# AFE.net
KiCad netlist of a schematic drawn in Altium Designer
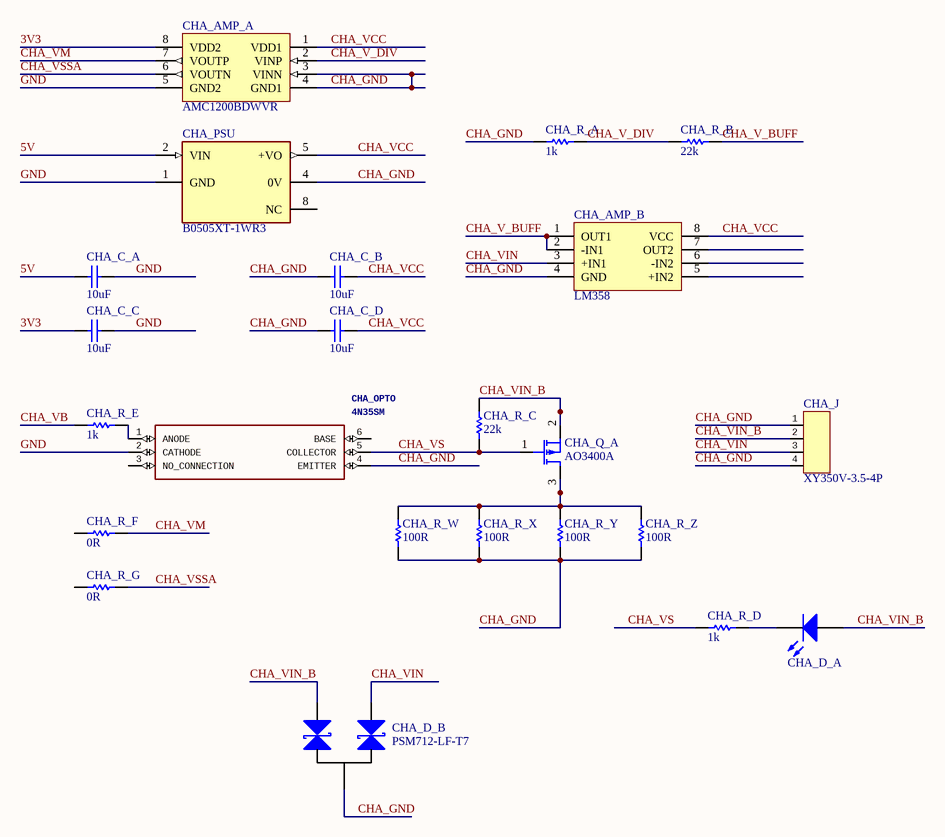
[diagram p0: AFE.SchDoc]

(export (version "E")
  (design (tool "Eeschema 10.0.6"))
  (components
    (comp (ref "CHA_AMP_A")
      (value "AMC1200BDWVR")
      (footprint "FOOTPRINTS:SOIC-8-P1.27-W7.5")
      (description "U - IC - 100KHz ISOLATION AMPLIFIER")
      (fields (field (name "LCSC PART #") "C79905"))
      (libsource (lib "JLC_PCB") (part "AMC1200BDWVR"))
    )
    (comp (ref "CHA_AMP_B")
      (value "LM358")
      (footprint "FOOTPRINTS:SOIC-8-P1.27-W3.5")
      (description "U - IC - OP AMP (DUAL)")
      (fields (field (name "LCSC PART #") "C63813"))
      (libsource (lib "JLC_PCB") (part "LMV358IDR"))
    )
    (comp (ref "CHA_C_A")
      (value "10uF")
      (footprint "C_0603")
      (description "C - CAPACITOR - MLCC - 10uF - 25V - 0603")
      (fields (field (name "LCSC PART #") "C96446") (field (name "Comment") "CL10A106MA8NRNC"))
      (libsource (lib "JLC_PCB") (part "CL10A106MA8NRNC"))
    )
    (comp (ref "CHA_C_B")
      (value "10uF")
      (footprint "C_0603")
      (description "C - CAPACITOR - MLCC - 10uF - 25V - 0603")
      (fields (field (name "LCSC PART #") "C96446") (field (name "Comment") "CL10A106MA8NRNC"))
      (libsource (lib "JLC_PCB") (part "CL10A106MA8NRNC"))
    )
    (comp (ref "CHA_C_C")
      (value "10uF")
      (footprint "C_0603")
      (description "C - CAPACITOR - MLCC - 10uF - 25V - 0603")
      (fields (field (name "LCSC PART #") "C96446") (field (name "Comment") "CL10A106MA8NRNC"))
      (libsource (lib "JLC_PCB") (part "CL10A106MA8NRNC"))
    )
    (comp (ref "CHA_C_D")
      (value "10uF")
      (footprint "C_0603")
      (description "C - CAPACITOR - MLCC - 10uF - 25V - 0603")
      (fields (field (name "LCSC PART #") "C96446") (field (name "Comment") "CL10A106MA8NRNC"))
      (libsource (lib "JLC_PCB") (part "CL10A106MA8NRNC"))
    )
    (comp (ref "CHA_D_A")
      (value "KT-0603R")
      (footprint "D_0603")
      (description "D - LED - 0603 - Red")
      (fields (field (name "LCSC PART #") "C2286"))
      (libsource (lib "JLC_PCB") (part "KT-0603R"))
    )
    (comp (ref "CHA_D_B")
      (value "PSM712-LF-T7")
      (footprint "TO-236AB")
      (description "D - DIODE - TVS x2 - 7.2V")
      (fields (field (name "LCSC PART #") "C32677"))
      (libsource (lib "JLC_PCB") (part "PSM712-LF-T7"))
    )
    (comp (ref "CHA_J")
      (value "XY350V-3.5-4P")
      (footprint "XY350V-3.5-4P")
      (description "J - JACK - TERMINAL - 4P - RIGHT - MALE")
      (fields (field (name "LCSC PART #") "C557656"))
      (libsource (lib "JLC_PCB") (part "XY350V-3.5-4P"))
    )
    (comp (ref "CHA_OPTO")
      (value "4N35SM")
      (footprint "SOT254P916X508-6N")
      (description "Q - OPTOCOUPLER - 4170 V - 100% CTR")
      (fields (field (name "LCSC PART #") "C258228"))
      (libsource (lib "JLC_PCB") (part "4N35SM"))
    )
    (comp (ref "CHA_PSU")
      (value "B0505XT-1WR3")
      (footprint "CONV_B0512XT-1WR3")
      (description "T - Isolated Module DC DC Converter 5 -> 5V 200mA - DIP")
      (fields (field (name "LCSC PART #") "C19188495") (field (name "MF") "EVISUN"))
      (libsource (lib "JLC_PCB") (part "B0505XT-1WR3"))
    )
    (comp (ref "CHA_Q_A")
      (value "AO3400A")
      (footprint "TO-236AB")
      (description "Q - TRANSISTOR - MOSFET (P) - 20V - 3.4A - 0.26 Ohm")
      (fields (field (name "LCSC PART #") "C20917"))
      (libsource (lib "JLC_PCB") (part "AO3400A"))
    )
    (comp (ref "CHA_R_A")
      (value "1k")
      (footprint "R_0603")
      (description "R - RESISTOR - SMD - 1k - 1% - 0603")
      (fields (field (name "LCSC PART #") "C21190") (field (name "Comment") "0603WAF1001T5E"))
      (libsource (lib "JLC_PCB") (part "0603WAF1001T5E"))
    )
    (comp (ref "CHA_R_B")
      (value "22k")
      (footprint "R_0603")
      (description "R - RESISTOR - SMD - 22k - 1% - 0603")
      (fields (field (name "LCSC PART #") "C31850") (field (name "Comment") "0603WAF2202T5E"))
      (libsource (lib "JLC_PCB") (part "0603WAF2202T5E"))
    )
    (comp (ref "CHA_R_C")
      (value "22k")
      (footprint "R_0603")
      (description "R - RESISTOR - SMD - 22k - 1% - 0603")
      (fields (field (name "LCSC PART #") "C31850") (field (name "Comment") "0603WAF2202T5E"))
      (libsource (lib "JLC_PCB") (part "0603WAF2202T5E"))
    )
    (comp (ref "CHA_R_D")
      (value "1k")
      (footprint "R_0603")
      (description "R - RESISTOR - SMD - 1k - 1% - 0603")
      (fields (field (name "LCSC PART #") "C21190") (field (name "Comment") "0603WAF1001T5E"))
      (libsource (lib "JLC_PCB") (part "0603WAF1001T5E"))
    )
    (comp (ref "CHA_R_E")
      (value "1k")
      (footprint "R_0603")
      (description "R - RESISTOR - SMD - 1k - 1% - 0603")
      (fields (field (name "LCSC PART #") "C21190") (field (name "Comment") "0603WAF1001T5E"))
      (libsource (lib "JLC_PCB") (part "0603WAF1001T5E"))
    )
    (comp (ref "CHA_R_F")
      (value "0R")
      (footprint "R_0603")
      (description "R - RESISTOR - SMD - 0R - 1% - 0603")
      (fields (field (name "LCSC PART #") "C21189") (field (name "Comment") "0603WAF0000T5E"))
      (libsource (lib "JLC_PCB") (part "0603WAF0000T5E"))
    )
    (comp (ref "CHA_R_G")
      (value "0R")
      (footprint "R_0603")
      (description "R - RESISTOR - SMD - 0R - 1% - 0603")
      (fields (field (name "LCSC PART #") "C21189") (field (name "Comment") "0603WAF0000T5E"))
      (libsource (lib "JLC_PCB") (part "0603WAF0000T5E"))
    )
    (comp (ref "CHA_R_W")
      (value "100R")
      (footprint "R_1206")
      (description "R - RESISTOR - SMD - 100R - 1% - 1206")
      (fields (field (name "LCSC PART #") "C17901") (field (name "Comment") "1206W4F1000T5E"))
      (libsource (lib "JLC_PCB") (part "1206W4F1000T5E"))
    )
    (comp (ref "CHA_R_X")
      (value "100R")
      (footprint "R_1206")
      (description "R - RESISTOR - SMD - 100R - 1% - 1206")
      (fields (field (name "LCSC PART #") "C17901") (field (name "Comment") "1206W4F1000T5E"))
      (libsource (lib "JLC_PCB") (part "1206W4F1000T5E"))
    )
    (comp (ref "CHA_R_Y")
      (value "100R")
      (footprint "R_1206")
      (description "R - RESISTOR - SMD - 100R - 1% - 1206")
      (fields (field (name "LCSC PART #") "C17901") (field (name "Comment") "1206W4F1000T5E"))
      (libsource (lib "JLC_PCB") (part "1206W4F1000T5E"))
    )
    (comp (ref "CHA_R_Z")
      (value "100R")
      (footprint "R_1206")
      (description "R - RESISTOR - SMD - 100R - 1% - 1206")
      (fields (field (name "LCSC PART #") "C17901") (field (name "Comment") "1206W4F1000T5E"))
      (libsource (lib "JLC_PCB") (part "1206W4F1000T5E"))
    )
  )
  (nets
    (net (code "1") (name "/3V3") (class "Default")
      (node (ref "CHA_AMP_A") (pin "8") (pinfunction "VDD2_8") (pintype "passive"))
      (node (ref "CHA_C_C") (pin "2") (pinfunction "2_2") (pintype "passive"))
    )
    (net (code "2") (name "/5V") (class "Default")
      (node (ref "CHA_C_A") (pin "2") (pinfunction "2_2") (pintype "passive"))
      (node (ref "CHA_PSU") (pin "2") (pinfunction "VIN_2") (pintype "input"))
    )
    (net (code "3") (name "/CHA_GND") (class "Default")
      (node (ref "CHA_AMP_A") (pin "3") (pinfunction "VINN_3") (pintype "input"))
      (node (ref "CHA_AMP_A") (pin "4") (pinfunction "GND1_4") (pintype "power_in"))
      (node (ref "CHA_AMP_B") (pin "4") (pinfunction "GND_4") (pintype "passive"))
      (node (ref "CHA_C_B") (pin "2") (pinfunction "2_2") (pintype "passive"))
      (node (ref "CHA_C_D") (pin "2") (pinfunction "2_2") (pintype "passive"))
      (node (ref "CHA_D_B") (pin "3") (pinfunction "A_3") (pintype "passive"))
      (node (ref "CHA_J") (pin "1") (pinfunction "1_1") (pintype "passive"))
      (node (ref "CHA_J") (pin "4") (pinfunction "4_4") (pintype "passive"))
      (node (ref "CHA_OPTO") (pin "4") (pinfunction "EMITTER_4") (pintype "bidirectional"))
      (node (ref "CHA_PSU") (pin "4") (pinfunction "0V_4") (pintype "passive"))
      (node (ref "CHA_R_A") (pin "1") (pinfunction "1_1") (pintype "passive"))
      (node (ref "CHA_R_W") (pin "1") (pinfunction "1_1") (pintype "passive"))
      (node (ref "CHA_R_X") (pin "1") (pinfunction "1_1") (pintype "passive"))
      (node (ref "CHA_R_Y") (pin "1") (pinfunction "1_1") (pintype "passive"))
      (node (ref "CHA_R_Z") (pin "1") (pinfunction "1_1") (pintype "passive"))
    )
    (net (code "4") (name "/CHA_VB") (class "Default")
      (node (ref "CHA_R_E") (pin "1") (pinfunction "1_1") (pintype "passive"))
    )
    (net (code "5") (name "/CHA_VCC") (class "Default")
      (node (ref "CHA_AMP_A") (pin "1") (pinfunction "VDD1_1") (pintype "passive"))
      (node (ref "CHA_AMP_B") (pin "8") (pinfunction "VCC_8") (pintype "passive"))
      (node (ref "CHA_C_B") (pin "1") (pinfunction "1_1") (pintype "passive"))
      (node (ref "CHA_C_D") (pin "1") (pinfunction "1_1") (pintype "passive"))
      (node (ref "CHA_PSU") (pin "5") (pinfunction "+VO_5") (pintype "output"))
    )
    (net (code "6") (name "/CHA_VIN") (class "Default")
      (node (ref "CHA_AMP_B") (pin "3") (pinfunction "+IN1_3") (pintype "passive"))
      (node (ref "CHA_D_B") (pin "2") (pinfunction "K_2") (pintype "passive"))
      (node (ref "CHA_J") (pin "3") (pinfunction "3_3") (pintype "passive"))
    )
    (net (code "7") (name "/CHA_VIN_B") (class "Default")
      (node (ref "CHA_D_A") (pin "2") (pinfunction "A_2") (pintype "passive"))
      (node (ref "CHA_D_B") (pin "1") (pinfunction "K_1") (pintype "passive"))
      (node (ref "CHA_J") (pin "2") (pinfunction "2_2") (pintype "passive"))
      (node (ref "CHA_Q_A") (pin "2") (pinfunction "S_2") (pintype "passive"))
      (node (ref "CHA_R_C") (pin "2") (pinfunction "2_2") (pintype "passive"))
    )
    (net (code "8") (name "/CHA_VM") (class "Default")
      (node (ref "CHA_AMP_A") (pin "7") (pinfunction "VOUTP_7") (pintype "output"))
      (node (ref "CHA_R_F") (pin "2") (pinfunction "2_2") (pintype "passive"))
    )
    (net (code "9") (name "/CHA_VS") (class "Default")
      (node (ref "CHA_OPTO") (pin "5") (pinfunction "COLLECTOR_5") (pintype "bidirectional"))
      (node (ref "CHA_Q_A") (pin "1") (pinfunction "G_1") (pintype "passive"))
      (node (ref "CHA_R_C") (pin "1") (pinfunction "1_1") (pintype "passive"))
      (node (ref "CHA_R_D") (pin "1") (pinfunction "1_1") (pintype "passive"))
    )
    (net (code "10") (name "/CHA_VSSA") (class "Default")
      (node (ref "CHA_AMP_A") (pin "6") (pinfunction "VOUTN_6") (pintype "output"))
      (node (ref "CHA_R_G") (pin "2") (pinfunction "2_2") (pintype "passive"))
    )
    (net (code "11") (name "/CHA_V_BUFF") (class "Default")
      (node (ref "CHA_AMP_B") (pin "1") (pinfunction "OUT1_1") (pintype "passive"))
      (node (ref "CHA_AMP_B") (pin "2") (pinfunction "-IN1_2") (pintype "passive"))
      (node (ref "CHA_R_B") (pin "2") (pinfunction "2_2") (pintype "passive"))
    )
    (net (code "12") (name "/CHA_V_DIV") (class "Default")
      (node (ref "CHA_AMP_A") (pin "2") (pinfunction "VINP_2") (pintype "input"))
      (node (ref "CHA_R_A") (pin "2") (pinfunction "2_2") (pintype "passive"))
      (node (ref "CHA_R_B") (pin "1") (pinfunction "1_1") (pintype "passive"))
    )
    (net (code "13") (name "/GND") (class "Default")
      (node (ref "CHA_AMP_A") (pin "5") (pinfunction "GND2_5") (pintype "power_in"))
      (node (ref "CHA_C_A") (pin "1") (pinfunction "1_1") (pintype "passive"))
      (node (ref "CHA_C_C") (pin "1") (pinfunction "1_1") (pintype "passive"))
      (node (ref "CHA_OPTO") (pin "2") (pinfunction "CATHODE_2") (pintype "bidirectional"))
      (node (ref "CHA_PSU") (pin "1") (pinfunction "GND_1") (pintype "power_in"))
    )
    (net (code "14") (name "Net-(CHA_D_A-K)") (class "Default")
      (node (ref "CHA_D_A") (pin "1") (pinfunction "K_1") (pintype "passive"))
      (node (ref "CHA_R_D") (pin "2") (pinfunction "2_2") (pintype "passive"))
    )
    (net (code "15") (name "Net-(CHA_OPTO-ANODE)") (class "Default")
      (node (ref "CHA_OPTO") (pin "1") (pinfunction "ANODE_1") (pintype "bidirectional"))
      (node (ref "CHA_R_E") (pin "2") (pinfunction "2_2") (pintype "passive"))
    )
    (net (code "16") (name "Net-(CHA_Q_A-D)") (class "Default")
      (node (ref "CHA_Q_A") (pin "3") (pinfunction "D_3") (pintype "passive"))
      (node (ref "CHA_R_W") (pin "2") (pinfunction "2_2") (pintype "passive"))
      (node (ref "CHA_R_X") (pin "2") (pinfunction "2_2") (pintype "passive"))
      (node (ref "CHA_R_Y") (pin "2") (pinfunction "2_2") (pintype "passive"))
      (node (ref "CHA_R_Z") (pin "2") (pinfunction "2_2") (pintype "passive"))
    )
    (net (code "17") (name "unconnected-(CHA_AMP_B-+IN2-Pad5)") (class "Default")
      (node (ref "CHA_AMP_B") (pin "5") (pinfunction "+IN2_5") (pintype "passive"))
    )
    (net (code "18") (name "unconnected-(CHA_AMP_B--IN2-Pad6)") (class "Default")
      (node (ref "CHA_AMP_B") (pin "6") (pinfunction "-IN2_6") (pintype "passive"))
    )
    (net (code "19") (name "unconnected-(CHA_AMP_B-OUT2-Pad7)") (class "Default")
      (node (ref "CHA_AMP_B") (pin "7") (pinfunction "OUT2_7") (pintype "passive"))
    )
    (net (code "20") (name "unconnected-(CHA_OPTO-BASE-Pad6)") (class "Default")
      (node (ref "CHA_OPTO") (pin "6") (pinfunction "BASE_6") (pintype "bidirectional"))
    )
    (net (code "21") (name "unconnected-(CHA_OPTO-NO_CONNECTION-Pad3)") (class "Default")
      (node (ref "CHA_OPTO") (pin "3") (pinfunction "NO_CONNECTION_3") (pintype "bidirectional"))
    )
    (net (code "22") (name "unconnected-(CHA_PSU-NC-Pad8)") (class "Default")
      (node (ref "CHA_PSU") (pin "8") (pinfunction "NC_8") (pintype "passive"))
    )
    (net (code "23") (name "unconnected-(CHA_R_F-Pad1)") (class "Default")
      (node (ref "CHA_R_F") (pin "1") (pinfunction "1_1") (pintype "passive"))
    )
    (net (code "24") (name "unconnected-(CHA_R_G-Pad1)") (class "Default")
      (node (ref "CHA_R_G") (pin "1") (pinfunction "1_1") (pintype "passive"))
    )
  )
)
